# esquema.net
KiCad netlist of a schematic drawn in Altium Designer
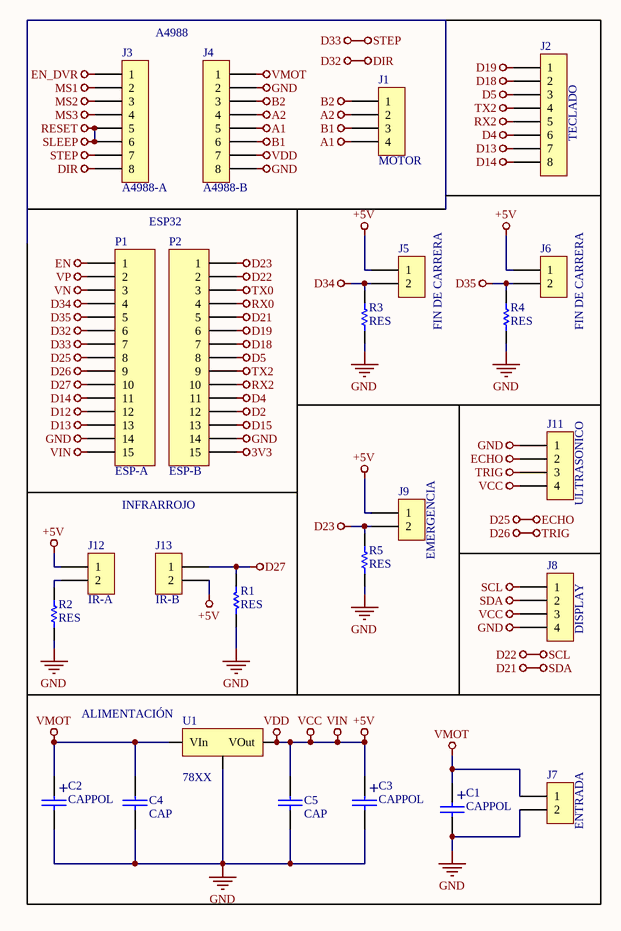
[diagram p0: esquema.SchDoc]

(export (version "E")
  (design (tool "Eeschema 10.0.6"))
  (components
    (comp (ref "C1") (value "CAPPOL") (footprint "CAP100RP2") (libsource (lib "LIB PIO IX") (part "CAPPOL")))
    (comp (ref "C2") (value "CAPPOL") (footprint "CAP100RP") (libsource (lib "LIB PIO IX") (part "CAPPOL")))
    (comp (ref "C3") (value "CAPPOL") (footprint "CAP100RP") (libsource (lib "LIB PIO IX") (part "CAPPOL")))
    (comp (ref "C4") (value "CAP") (footprint "CAP200") (libsource (lib "LIB PIO IX") (part "CAP")))
    (comp (ref "C5") (value "CAP") (footprint "CAP200") (libsource (lib "LIB PIO IX") (part "CAP")))
    (comp (ref "J1") (value "MOTOR") (footprint "SIP4") (libsource (lib "LIB PIO IX") (part "CON4")))
    (comp (ref "J2") (value "TECLADO") (footprint "SIP8") (libsource (lib "LIB PIO IX") (part "CON8")))
    (comp (ref "J3") (value "A4988-A") (footprint "SIP8") (libsource (lib "LIB PIO IX") (part "CON8")))
    (comp (ref "J4") (value "A4988-B") (footprint "SIP8") (libsource (lib "") (part "CON8_1")))
    (comp (ref "J5") (value "FIN DE CARRERA") (footprint "SIP2") (libsource (lib "LIBEBAL") (part "CON2")))
    (comp (ref "J6") (value "FIN DE CARRERA") (footprint "SIP2") (libsource (lib "LIBEBAL") (part "CON2")))
    (comp (ref "J7")
      (value "ENTRADA")
      (footprint "BORNERA2")
      (libsource (lib "LIB PIO IX") (part "BORNERA 2"))
    )
    (comp (ref "J8") (value "DISPLAY") (footprint "SIP4") (libsource (lib "LIB PIO IX") (part "CON4")))
    (comp (ref "J9") (value "EMERGENCIA") (footprint "SIP2") (libsource (lib "LIBEBAL") (part "CON2")))
    (comp (ref "J11") (value "ULTRASONICO") (footprint "SIP4") (libsource (lib "LIB PIO IX") (part "CON4")))
    (comp (ref "J12") (value "IR-A") (footprint "SIP2") (libsource (lib "LIBEBAL") (part "CON2")))
    (comp (ref "J13") (value "IR-B") (footprint "SIP2") (libsource (lib "") (part "CON2_1")))
    (comp (ref "P1")
      (value "ESP-A")
      (footprint "HDR1X15")
      (description "Header, 15-Pin")
      (fields (field (name "PUBLISHER") "Altium Limited"))
      (libsource (lib "") (part "Header 15_1"))
    )
    (comp (ref "P2")
      (value "ESP-B")
      (footprint "HDR1X15")
      (description "Header, 15-Pin")
      (fields (field (name "PUBLISHER") "Altium Limited"))
      (libsource (lib "Miscellaneous Connectors") (part "Header 15"))
    )
    (comp (ref "R1") (value "RES") (footprint "RES400") (libsource (lib "LIBEBAL") (part "RES")))
    (comp (ref "R2") (value "RES") (footprint "RES400") (libsource (lib "LIBEBAL") (part "RES")))
    (comp (ref "R3") (value "RES") (footprint "RES400") (libsource (lib "LIBEBAL") (part "RES")))
    (comp (ref "R4") (value "RES") (footprint "RES400") (libsource (lib "LIBEBAL") (part "RES")))
    (comp (ref "R5") (value "RES") (footprint "RES400") (libsource (lib "LIBEBAL") (part "RES")))
    (comp (ref "U1")
      (value "78XX")
      (footprint "TO-220 V")
      (description "REGULDOR POSITIVO")
      (libsource (lib "LIB PIO IX") (part "78XX"))
    )
  )
  (nets
    (net (code "1") (name "+5V") (class "Default")
      (node (ref "C3") (pin "1") (pinfunction "1_1") (pintype "passive"))
      (node (ref "C5") (pin "1") (pinfunction "1_1") (pintype "passive"))
      (node (ref "J11") (pin "4") (pinfunction "4_4") (pintype "passive"))
      (node (ref "J12") (pin "1") (pinfunction "1_1") (pintype "passive"))
      (node (ref "J13") (pin "2") (pinfunction "2_2") (pintype "passive"))
      (node (ref "J4") (pin "7") (pinfunction "7_7") (pintype "passive"))
      (node (ref "J5") (pin "1") (pinfunction "1_1") (pintype "passive"))
      (node (ref "J6") (pin "1") (pinfunction "1_1") (pintype "passive"))
      (node (ref "J8") (pin "3") (pinfunction "3_3") (pintype "passive"))
      (node (ref "J9") (pin "1") (pinfunction "1_1") (pintype "passive"))
      (node (ref "P1") (pin "15") (pinfunction "15_15") (pintype "passive"))
      (node (ref "U1") (pin "3") (pinfunction "VOut_3") (pintype "passive"))
    )
    (net (code "2") (name "3V3") (class "Default")
      (node (ref "P2") (pin "15") (pinfunction "15_15") (pintype "passive"))
    )
    (net (code "3") (name "A1") (class "Default")
      (node (ref "J1") (pin "4") (pinfunction "4_4") (pintype "passive"))
      (node (ref "J4") (pin "5") (pinfunction "5_5") (pintype "passive"))
    )
    (net (code "4") (name "A2") (class "Default")
      (node (ref "J1") (pin "2") (pinfunction "2_2") (pintype "passive"))
      (node (ref "J4") (pin "4") (pinfunction "4_4") (pintype "passive"))
    )
    (net (code "5") (name "B1") (class "Default")
      (node (ref "J1") (pin "3") (pinfunction "3_3") (pintype "passive"))
      (node (ref "J4") (pin "6") (pinfunction "6_6") (pintype "passive"))
    )
    (net (code "6") (name "B2") (class "Default")
      (node (ref "J1") (pin "1") (pinfunction "1_1") (pintype "passive"))
      (node (ref "J4") (pin "3") (pinfunction "3_3") (pintype "passive"))
    )
    (net (code "7") (name "D2") (class "Default")
      (node (ref "P2") (pin "12") (pinfunction "12_12") (pintype "passive"))
    )
    (net (code "8") (name "D4") (class "Default")
      (node (ref "J2") (pin "6") (pinfunction "6_6") (pintype "passive"))
      (node (ref "P2") (pin "11") (pinfunction "11_11") (pintype "passive"))
    )
    (net (code "9") (name "D5") (class "Default")
      (node (ref "J2") (pin "3") (pinfunction "3_3") (pintype "passive"))
      (node (ref "P2") (pin "8") (pinfunction "8_8") (pintype "passive"))
    )
    (net (code "10") (name "D12") (class "Default")
      (node (ref "P1") (pin "12") (pinfunction "12_12") (pintype "passive"))
    )
    (net (code "11") (name "D13") (class "Default")
      (node (ref "J2") (pin "7") (pinfunction "7_7") (pintype "passive"))
      (node (ref "P1") (pin "13") (pinfunction "13_13") (pintype "passive"))
    )
    (net (code "12") (name "D14") (class "Default")
      (node (ref "J2") (pin "8") (pinfunction "8_8") (pintype "passive"))
      (node (ref "P1") (pin "11") (pinfunction "11_11") (pintype "passive"))
    )
    (net (code "13") (name "D15") (class "Default")
      (node (ref "P2") (pin "13") (pinfunction "13_13") (pintype "passive"))
    )
    (net (code "14") (name "D18") (class "Default")
      (node (ref "J2") (pin "2") (pinfunction "2_2") (pintype "passive"))
      (node (ref "P2") (pin "7") (pinfunction "7_7") (pintype "passive"))
    )
    (net (code "15") (name "D19") (class "Default")
      (node (ref "J2") (pin "1") (pinfunction "1_1") (pintype "passive"))
      (node (ref "P2") (pin "6") (pinfunction "6_6") (pintype "passive"))
    )
    (net (code "16") (name "D21") (class "Default")
      (node (ref "J8") (pin "2") (pinfunction "2_2") (pintype "passive"))
      (node (ref "P2") (pin "5") (pinfunction "5_5") (pintype "passive"))
    )
    (net (code "17") (name "D22") (class "Default")
      (node (ref "J8") (pin "1") (pinfunction "1_1") (pintype "passive"))
      (node (ref "P2") (pin "2") (pinfunction "2_2") (pintype "passive"))
    )
    (net (code "18") (name "D23") (class "Default")
      (node (ref "J9") (pin "2") (pinfunction "2_2") (pintype "passive"))
      (node (ref "P2") (pin "1") (pinfunction "1_1") (pintype "passive"))
      (node (ref "R5") (pin "2") (pinfunction "2_2") (pintype "passive"))
    )
    (net (code "19") (name "D25") (class "Default")
      (node (ref "J11") (pin "2") (pinfunction "2_2") (pintype "passive"))
      (node (ref "P1") (pin "8") (pinfunction "8_8") (pintype "passive"))
    )
    (net (code "20") (name "D26") (class "Default")
      (node (ref "J11") (pin "3") (pinfunction "3_3") (pintype "passive"))
      (node (ref "P1") (pin "9") (pinfunction "9_9") (pintype "passive"))
    )
    (net (code "21") (name "D27") (class "Default")
      (node (ref "J13") (pin "1") (pinfunction "1_1") (pintype "passive"))
      (node (ref "P1") (pin "10") (pinfunction "10_10") (pintype "passive"))
      (node (ref "R1") (pin "2") (pinfunction "2_2") (pintype "passive"))
    )
    (net (code "22") (name "D32") (class "Default")
      (node (ref "J3") (pin "8") (pinfunction "8_8") (pintype "passive"))
      (node (ref "P1") (pin "6") (pinfunction "6_6") (pintype "passive"))
    )
    (net (code "23") (name "D33") (class "Default")
      (node (ref "J3") (pin "7") (pinfunction "7_7") (pintype "passive"))
      (node (ref "P1") (pin "7") (pinfunction "7_7") (pintype "passive"))
    )
    (net (code "24") (name "D34") (class "Default")
      (node (ref "J5") (pin "2") (pinfunction "2_2") (pintype "passive"))
      (node (ref "P1") (pin "4") (pinfunction "4_4") (pintype "passive"))
      (node (ref "R3") (pin "2") (pinfunction "2_2") (pintype "passive"))
    )
    (net (code "25") (name "D35") (class "Default")
      (node (ref "J6") (pin "2") (pinfunction "2_2") (pintype "passive"))
      (node (ref "P1") (pin "5") (pinfunction "5_5") (pintype "passive"))
      (node (ref "R4") (pin "2") (pinfunction "2_2") (pintype "passive"))
    )
    (net (code "26") (name "EN") (class "Default")
      (node (ref "P1") (pin "1") (pinfunction "1_1") (pintype "passive"))
    )
    (net (code "27") (name "EN_DVR") (class "Default")
      (node (ref "J3") (pin "1") (pinfunction "1_1") (pintype "passive"))
    )
    (net (code "28") (name "GND") (class "Default")
      (node (ref "C1") (pin "2") (pinfunction "2_2") (pintype "passive"))
      (node (ref "C2") (pin "2") (pinfunction "2_2") (pintype "passive"))
      (node (ref "C3") (pin "2") (pinfunction "2_2") (pintype "passive"))
      (node (ref "C4") (pin "2") (pinfunction "2_2") (pintype "passive"))
      (node (ref "C5") (pin "2") (pinfunction "2_2") (pintype "passive"))
      (node (ref "J11") (pin "1") (pinfunction "1_1") (pintype "passive"))
      (node (ref "J4") (pin "2") (pinfunction "2_2") (pintype "passive"))
      (node (ref "J4") (pin "8") (pinfunction "8_8") (pintype "passive"))
      (node (ref "J7") (pin "2") (pinfunction "2_2") (pintype "passive"))
      (node (ref "J8") (pin "4") (pinfunction "4_4") (pintype "passive"))
      (node (ref "P1") (pin "14") (pinfunction "14_14") (pintype "passive"))
      (node (ref "P2") (pin "14") (pinfunction "14_14") (pintype "passive"))
      (node (ref "R1") (pin "1") (pinfunction "1_1") (pintype "passive"))
      (node (ref "R2") (pin "1") (pinfunction "1_1") (pintype "passive"))
      (node (ref "R3") (pin "1") (pinfunction "1_1") (pintype "passive"))
      (node (ref "R4") (pin "1") (pinfunction "1_1") (pintype "passive"))
      (node (ref "R5") (pin "1") (pinfunction "1_1") (pintype "passive"))
      (node (ref "U1") (pin "2") (pinfunction "GND_2") (pintype "passive"))
    )
    (net (code "29") (name "MS1") (class "Default")
      (node (ref "J3") (pin "2") (pinfunction "2_2") (pintype "passive"))
    )
    (net (code "30") (name "MS2") (class "Default")
      (node (ref "J3") (pin "3") (pinfunction "3_3") (pintype "passive"))
    )
    (net (code "31") (name "MS3") (class "Default")
      (node (ref "J3") (pin "4") (pinfunction "4_4") (pintype "passive"))
    )
    (net (code "32") (name "Net-(J12-Pad2)") (class "Default")
      (node (ref "J12") (pin "2") (pinfunction "2_2") (pintype "passive"))
      (node (ref "R2") (pin "2") (pinfunction "2_2") (pintype "passive"))
    )
    (net (code "33") (name "RESET") (class "Default")
      (node (ref "J3") (pin "5") (pinfunction "5_5") (pintype "passive"))
      (node (ref "J3") (pin "6") (pinfunction "6_6") (pintype "passive"))
    )
    (net (code "34") (name "RX0") (class "Default")
      (node (ref "P2") (pin "4") (pinfunction "4_4") (pintype "passive"))
    )
    (net (code "35") (name "RX2") (class "Default")
      (node (ref "J2") (pin "5") (pinfunction "5_5") (pintype "passive"))
      (node (ref "P2") (pin "10") (pinfunction "10_10") (pintype "passive"))
    )
    (net (code "36") (name "TX0") (class "Default")
      (node (ref "P2") (pin "3") (pinfunction "3_3") (pintype "passive"))
    )
    (net (code "37") (name "TX2") (class "Default")
      (node (ref "J2") (pin "4") (pinfunction "4_4") (pintype "passive"))
      (node (ref "P2") (pin "9") (pinfunction "9_9") (pintype "passive"))
    )
    (net (code "38") (name "VMOT") (class "Default")
      (node (ref "C1") (pin "1") (pinfunction "1_1") (pintype "passive"))
      (node (ref "C2") (pin "1") (pinfunction "1_1") (pintype "passive"))
      (node (ref "C4") (pin "1") (pinfunction "1_1") (pintype "passive"))
      (node (ref "J4") (pin "1") (pinfunction "1_1") (pintype "passive"))
      (node (ref "J7") (pin "1") (pinfunction "1_1") (pintype "passive"))
      (node (ref "U1") (pin "1") (pinfunction "VIn_1") (pintype "passive"))
    )
    (net (code "39") (name "VN") (class "Default")
      (node (ref "P1") (pin "3") (pinfunction "3_3") (pintype "passive"))
    )
    (net (code "40") (name "VP") (class "Default")
      (node (ref "P1") (pin "2") (pinfunction "2_2") (pintype "passive"))
    )
  )
)
